# Control_Board.net
KiCad netlist of a schematic drawn in EAGLE
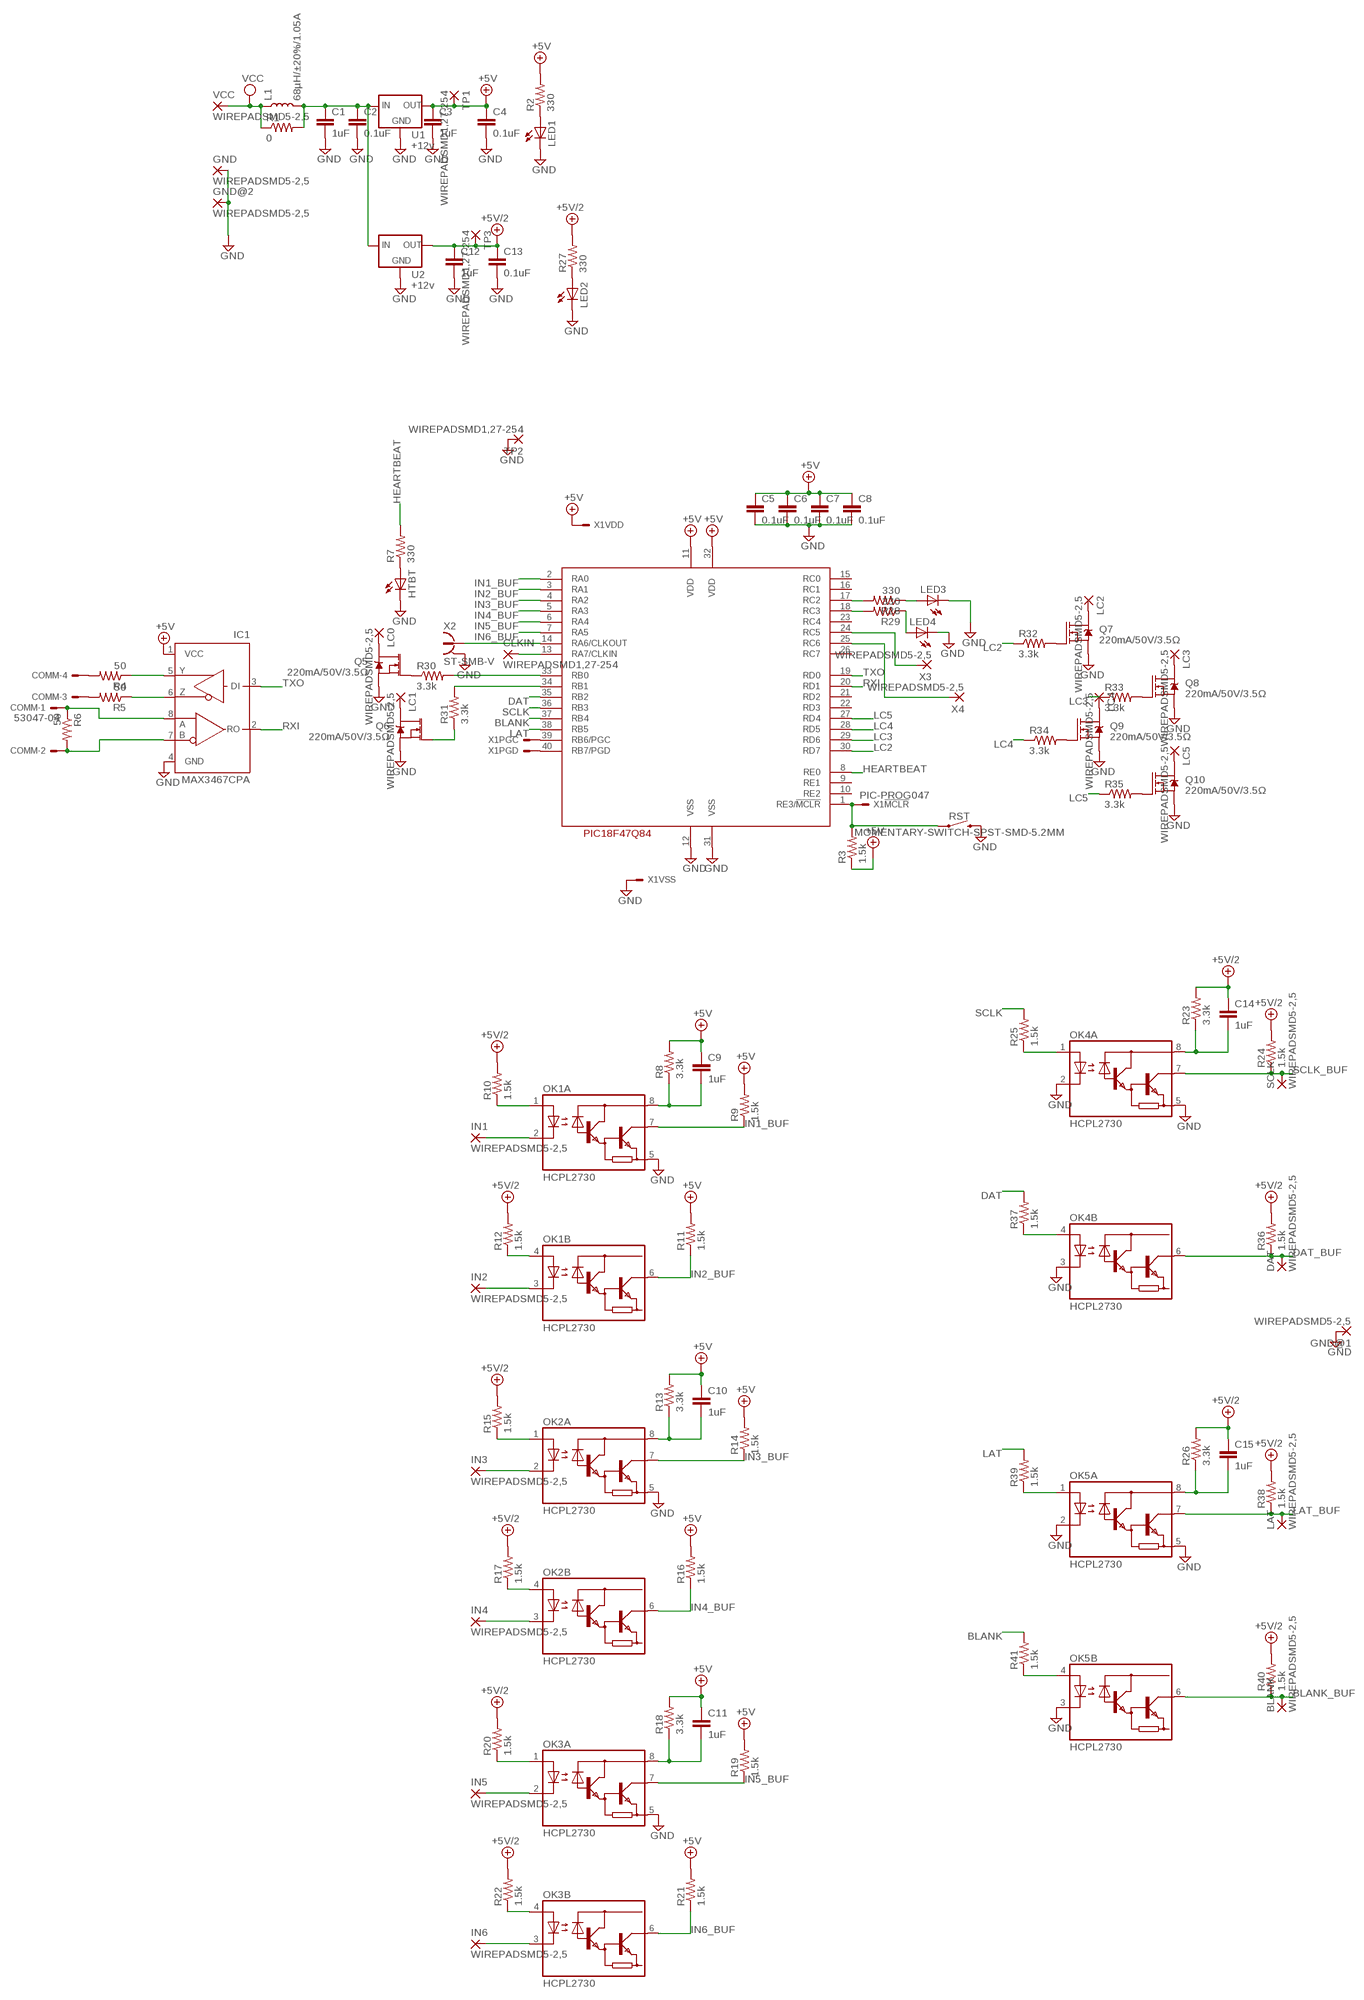
[diagram p0: schematic, sheet 1]

(export (version "E")
  (design (tool "Eeschema 10.0.6"))
  (components
    (comp (ref "BLANK")
      (value "WIREPADSMD5-2,5")
      (footprint "eagle-import:5-2,5")
      (libsource (lib "eagle-import") (part "WIREPADSMD5-2,5"))
    )
    (comp (ref "C1")
      (value "1uF")
      (footprint "eagle-import:C1206")
      (libsource (lib "eagle-import") (part "C-EUC1206"))
    )
    (comp (ref "C2")
      (value "0.1uF")
      (footprint "eagle-import:C1206")
      (libsource (lib "eagle-import") (part "C-EUC1206"))
    )
    (comp (ref "C3")
      (value "1uF")
      (footprint "eagle-import:C1206")
      (libsource (lib "eagle-import") (part "C-EUC1206"))
    )
    (comp (ref "C4")
      (value "0.1uF")
      (footprint "eagle-import:C1206")
      (libsource (lib "eagle-import") (part "C-EUC1206"))
    )
    (comp (ref "C5")
      (value "0.1uF")
      (footprint "eagle-import:C1206")
      (libsource (lib "eagle-import") (part "C-EUC1206"))
    )
    (comp (ref "C6")
      (value "0.1uF")
      (footprint "eagle-import:C1206")
      (libsource (lib "eagle-import") (part "C-EUC1206"))
    )
    (comp (ref "C7")
      (value "0.1uF")
      (footprint "eagle-import:C1206")
      (libsource (lib "eagle-import") (part "C-EUC1206"))
    )
    (comp (ref "C8")
      (value "0.1uF")
      (footprint "eagle-import:C1206")
      (libsource (lib "eagle-import") (part "C-EUC1206"))
    )
    (comp (ref "C9")
      (value "1uF")
      (footprint "eagle-import:C1206")
      (libsource (lib "eagle-import") (part "C-EUC1206"))
    )
    (comp (ref "C10")
      (value "1uF")
      (footprint "eagle-import:C1206")
      (libsource (lib "eagle-import") (part "C-EUC1206"))
    )
    (comp (ref "C11")
      (value "1uF")
      (footprint "eagle-import:C1206")
      (libsource (lib "eagle-import") (part "C-EUC1206"))
    )
    (comp (ref "C12")
      (value "1uF")
      (footprint "eagle-import:C1206")
      (libsource (lib "eagle-import") (part "C-EUC1206"))
    )
    (comp (ref "C13")
      (value "0.1uF")
      (footprint "eagle-import:C1206")
      (libsource (lib "eagle-import") (part "C-EUC1206"))
    )
    (comp (ref "C14")
      (value "1uF")
      (footprint "eagle-import:C1206")
      (libsource (lib "eagle-import") (part "C-EUC1206"))
    )
    (comp (ref "C15")
      (value "1uF")
      (footprint "eagle-import:C1206")
      (libsource (lib "eagle-import") (part "C-EUC1206"))
    )
    (comp (ref "CLKIN")
      (value "WIREPADSMD1,27-254")
      (footprint "eagle-import:SMD1,27-2,54")
      (libsource (lib "eagle-import") (part "WIREPADSMD1,27-254"))
    )
    (comp (ref "COMM")
      (value "53047-04")
      (footprint "eagle-import:53047-04")
      (fields (field (name "MF") "WALDOM/MOLEX") (field (name "MPN") "53047-0410"))
      (libsource (lib "eagle-import") (part "53?-04047"))
    )
    (comp (ref "DAT")
      (value "WIREPADSMD5-2,5")
      (footprint "eagle-import:5-2,5")
      (libsource (lib "eagle-import") (part "WIREPADSMD5-2,5"))
    )
    (comp (ref "GND")
      (value "WIREPADSMD5-2,5")
      (footprint "eagle-import:5-2,5")
      (libsource (lib "eagle-import") (part "WIREPADSMD5-2,5"))
    )
    (comp (ref "GND@1")
      (value "WIREPADSMD5-2,5")
      (footprint "eagle-import:5-2,5")
      (libsource (lib "eagle-import") (part "WIREPADSMD5-2,5"))
    )
    (comp (ref "GND@2")
      (value "WIREPADSMD5-2,5")
      (footprint "eagle-import:5-2,5")
      (libsource (lib "eagle-import") (part "WIREPADSMD5-2,5"))
    )
    (comp (ref "HTBT")
      (value "LEDCHIPLED_1206")
      (footprint "eagle-import:CHIPLED_1206")
      (libsource (lib "eagle-import") (part "LEDCHIPLED_1206"))
    )
    (comp (ref "IC1")
      (value "MAX3467CPA")
      (footprint "eagle-import:SO08")
      (libsource (lib "eagle-import") (part "MAX3467PAC"))
    )
    (comp (ref "IN1")
      (value "WIREPADSMD5-2,5")
      (footprint "eagle-import:5-2,5")
      (libsource (lib "eagle-import") (part "WIREPADSMD5-2,5"))
    )
    (comp (ref "IN2")
      (value "WIREPADSMD5-2,5")
      (footprint "eagle-import:5-2,5")
      (libsource (lib "eagle-import") (part "WIREPADSMD5-2,5"))
    )
    (comp (ref "IN3")
      (value "WIREPADSMD5-2,5")
      (footprint "eagle-import:5-2,5")
      (libsource (lib "eagle-import") (part "WIREPADSMD5-2,5"))
    )
    (comp (ref "IN4")
      (value "WIREPADSMD5-2,5")
      (footprint "eagle-import:5-2,5")
      (libsource (lib "eagle-import") (part "WIREPADSMD5-2,5"))
    )
    (comp (ref "IN5")
      (value "WIREPADSMD5-2,5")
      (footprint "eagle-import:5-2,5")
      (libsource (lib "eagle-import") (part "WIREPADSMD5-2,5"))
    )
    (comp (ref "IN6")
      (value "WIREPADSMD5-2,5")
      (footprint "eagle-import:5-2,5")
      (libsource (lib "eagle-import") (part "WIREPADSMD5-2,5"))
    )
    (comp (ref "L1")
      (value "68µH/±20%/1.05A")
      (footprint "eagle-import:CR75")
      (libsource (lib "eagle-import") (part "INDUCTOR-CR75-68UH"))
    )
    (comp (ref "LAT")
      (value "WIREPADSMD5-2,5")
      (footprint "eagle-import:5-2,5")
      (libsource (lib "eagle-import") (part "WIREPADSMD5-2,5"))
    )
    (comp (ref "LC0")
      (value "WIREPADSMD5-2,5")
      (footprint "eagle-import:5-2,5")
      (libsource (lib "eagle-import") (part "WIREPADSMD5-2,5"))
    )
    (comp (ref "LC1")
      (value "WIREPADSMD5-2,5")
      (footprint "eagle-import:5-2,5")
      (libsource (lib "eagle-import") (part "WIREPADSMD5-2,5"))
    )
    (comp (ref "LC2")
      (value "WIREPADSMD5-2,5")
      (footprint "eagle-import:5-2,5")
      (libsource (lib "eagle-import") (part "WIREPADSMD5-2,5"))
    )
    (comp (ref "LC3")
      (value "WIREPADSMD5-2,5")
      (footprint "eagle-import:5-2,5")
      (libsource (lib "eagle-import") (part "WIREPADSMD5-2,5"))
    )
    (comp (ref "LC4")
      (value "WIREPADSMD5-2,5")
      (footprint "eagle-import:5-2,5")
      (libsource (lib "eagle-import") (part "WIREPADSMD5-2,5"))
    )
    (comp (ref "LC5")
      (value "WIREPADSMD5-2,5")
      (footprint "eagle-import:5-2,5")
      (libsource (lib "eagle-import") (part "WIREPADSMD5-2,5"))
    )
    (comp (ref "LED1")
      (value "LEDCHIPLED_1206")
      (footprint "eagle-import:CHIPLED_1206")
      (libsource (lib "eagle-import") (part "LEDCHIPLED_1206"))
    )
    (comp (ref "LED2")
      (value "LEDCHIPLED_1206")
      (footprint "eagle-import:CHIPLED_1206")
      (libsource (lib "eagle-import") (part "LEDCHIPLED_1206"))
    )
    (comp (ref "LED3")
      (value "LEDCHIPLED_1206")
      (footprint "eagle-import:CHIPLED_1206")
      (libsource (lib "eagle-import") (part "LEDCHIPLED_1206"))
    )
    (comp (ref "LED4")
      (value "LEDCHIPLED_1206")
      (footprint "eagle-import:CHIPLED_1206")
      (libsource (lib "eagle-import") (part "LEDCHIPLED_1206"))
    )
    (comp (ref "OK1")
      (value "HCPL2730")
      (footprint "eagle-import:DIL08")
      (fields (field (name "MF") "AGILENT TECHNOLOGIES") (field (name "MPN") "HCPL-2730-000E"))
      (libsource (lib "eagle-import") (part "HCPL2730"))
    )
    (comp (ref "OK2")
      (value "HCPL2730")
      (footprint "eagle-import:DIL08")
      (fields (field (name "MF") "AGILENT TECHNOLOGIES") (field (name "MPN") "HCPL-2730-000E"))
      (libsource (lib "eagle-import") (part "HCPL2730"))
    )
    (comp (ref "OK3")
      (value "HCPL2730")
      (footprint "eagle-import:DIL08")
      (fields (field (name "MF") "AGILENT TECHNOLOGIES") (field (name "MPN") "HCPL-2730-000E"))
      (libsource (lib "eagle-import") (part "HCPL2730"))
    )
    (comp (ref "OK4")
      (value "HCPL2730")
      (footprint "eagle-import:DIL08")
      (fields (field (name "MF") "AGILENT TECHNOLOGIES") (field (name "MPN") "HCPL-2730-000E"))
      (libsource (lib "eagle-import") (part "HCPL2730"))
    )
    (comp (ref "OK5")
      (value "HCPL2730")
      (footprint "eagle-import:DIL08")
      (fields (field (name "MF") "AGILENT TECHNOLOGIES") (field (name "MPN") "HCPL-2730-000E"))
      (libsource (lib "eagle-import") (part "HCPL2730"))
    )
    (comp (ref "Q5")
      (value "220mA/50V/3.5Ω")
      (footprint "eagle-import:SOT23-3")
      (libsource (lib "eagle-import") (part "MOSFET-NCH-BSS138"))
    )
    (comp (ref "Q6")
      (value "220mA/50V/3.5Ω")
      (footprint "eagle-import:SOT23-3")
      (libsource (lib "eagle-import") (part "MOSFET-NCH-BSS138"))
    )
    (comp (ref "Q7")
      (value "220mA/50V/3.5Ω")
      (footprint "eagle-import:SOT23-3")
      (libsource (lib "eagle-import") (part "MOSFET-NCH-BSS138"))
    )
    (comp (ref "Q8")
      (value "220mA/50V/3.5Ω")
      (footprint "eagle-import:SOT23-3")
      (libsource (lib "eagle-import") (part "MOSFET-NCH-BSS138"))
    )
    (comp (ref "Q9")
      (value "220mA/50V/3.5Ω")
      (footprint "eagle-import:SOT23-3")
      (libsource (lib "eagle-import") (part "MOSFET-NCH-BSS138"))
    )
    (comp (ref "Q10")
      (value "220mA/50V/3.5Ω")
      (footprint "eagle-import:SOT23-3")
      (libsource (lib "eagle-import") (part "MOSFET-NCH-BSS138"))
    )
    (comp (ref "R1")
      (value "0")
      (footprint "eagle-import:M1206")
      (libsource (lib "eagle-import") (part "R-US_M1206"))
    )
    (comp (ref "R2")
      (value "330")
      (footprint "eagle-import:M1206")
      (libsource (lib "eagle-import") (part "R-US_M1206"))
    )
    (comp (ref "R3")
      (value "1.5k")
      (footprint "eagle-import:M1206")
      (libsource (lib "eagle-import") (part "R-US_M1206"))
    )
    (comp (ref "R4")
      (value "50")
      (footprint "eagle-import:M1206")
      (libsource (lib "eagle-import") (part "R-US_M1206"))
    )
    (comp (ref "R5")
      (value "50")
      (footprint "eagle-import:M1206")
      (libsource (lib "eagle-import") (part "R-US_M1206"))
    )
    (comp (ref "R6")
      (value "50")
      (footprint "eagle-import:M1206")
      (libsource (lib "eagle-import") (part "R-US_M1206"))
    )
    (comp (ref "R7")
      (value "330")
      (footprint "eagle-import:M1206")
      (libsource (lib "eagle-import") (part "R-US_M1206"))
    )
    (comp (ref "R8")
      (value "3.3k")
      (footprint "eagle-import:M1206")
      (libsource (lib "eagle-import") (part "R-US_M1206"))
    )
    (comp (ref "R9")
      (value "1.5k")
      (footprint "eagle-import:M1206")
      (libsource (lib "eagle-import") (part "R-US_M1206"))
    )
    (comp (ref "R10")
      (value "1.5k")
      (footprint "eagle-import:M1206")
      (libsource (lib "eagle-import") (part "R-US_M1206"))
    )
    (comp (ref "R11")
      (value "1.5k")
      (footprint "eagle-import:M1206")
      (libsource (lib "eagle-import") (part "R-US_M1206"))
    )
    (comp (ref "R12")
      (value "1.5k")
      (footprint "eagle-import:M1206")
      (libsource (lib "eagle-import") (part "R-US_M1206"))
    )
    (comp (ref "R13")
      (value "3.3k")
      (footprint "eagle-import:M1206")
      (libsource (lib "eagle-import") (part "R-US_M1206"))
    )
    (comp (ref "R14")
      (value "1.5k")
      (footprint "eagle-import:M1206")
      (libsource (lib "eagle-import") (part "R-US_M1206"))
    )
    (comp (ref "R15")
      (value "1.5k")
      (footprint "eagle-import:M1206")
      (libsource (lib "eagle-import") (part "R-US_M1206"))
    )
    (comp (ref "R16")
      (value "1.5k")
      (footprint "eagle-import:M1206")
      (libsource (lib "eagle-import") (part "R-US_M1206"))
    )
    (comp (ref "R17")
      (value "1.5k")
      (footprint "eagle-import:M1206")
      (libsource (lib "eagle-import") (part "R-US_M1206"))
    )
    (comp (ref "R18")
      (value "3.3k")
      (footprint "eagle-import:M1206")
      (libsource (lib "eagle-import") (part "R-US_M1206"))
    )
    (comp (ref "R19")
      (value "1.5k")
      (footprint "eagle-import:M1206")
      (libsource (lib "eagle-import") (part "R-US_M1206"))
    )
    (comp (ref "R20")
      (value "1.5k")
      (footprint "eagle-import:M1206")
      (libsource (lib "eagle-import") (part "R-US_M1206"))
    )
    (comp (ref "R21")
      (value "1.5k")
      (footprint "eagle-import:M1206")
      (libsource (lib "eagle-import") (part "R-US_M1206"))
    )
    (comp (ref "R22")
      (value "1.5k")
      (footprint "eagle-import:M1206")
      (libsource (lib "eagle-import") (part "R-US_M1206"))
    )
    (comp (ref "R23")
      (value "3.3k")
      (footprint "eagle-import:M1206")
      (libsource (lib "eagle-import") (part "R-US_M1206"))
    )
    (comp (ref "R24")
      (value "1.5k")
      (footprint "eagle-import:M1206")
      (libsource (lib "eagle-import") (part "R-US_M1206"))
    )
    (comp (ref "R25")
      (value "1.5k")
      (footprint "eagle-import:M1206")
      (libsource (lib "eagle-import") (part "R-US_M1206"))
    )
    (comp (ref "R26")
      (value "3.3k")
      (footprint "eagle-import:M1206")
      (libsource (lib "eagle-import") (part "R-US_M1206"))
    )
    (comp (ref "R27")
      (value "330")
      (footprint "eagle-import:M1206")
      (libsource (lib "eagle-import") (part "R-US_M1206"))
    )
    (comp (ref "R28")
      (value "330")
      (footprint "eagle-import:M1206")
      (libsource (lib "eagle-import") (part "R-US_M1206"))
    )
    (comp (ref "R29")
      (value "330")
      (footprint "eagle-import:M1206")
      (libsource (lib "eagle-import") (part "R-US_M1206"))
    )
    (comp (ref "R30")
      (value "3.3k")
      (footprint "eagle-import:M1206")
      (libsource (lib "eagle-import") (part "R-US_M1206"))
    )
    (comp (ref "R31")
      (value "3.3k")
      (footprint "eagle-import:M1206")
      (libsource (lib "eagle-import") (part "R-US_M1206"))
    )
    (comp (ref "R32")
      (value "3.3k")
      (footprint "eagle-import:M1206")
      (libsource (lib "eagle-import") (part "R-US_M1206"))
    )
    (comp (ref "R33")
      (value "3.3k")
      (footprint "eagle-import:M1206")
      (libsource (lib "eagle-import") (part "R-US_M1206"))
    )
    (comp (ref "R34")
      (value "3.3k")
      (footprint "eagle-import:M1206")
      (libsource (lib "eagle-import") (part "R-US_M1206"))
    )
    (comp (ref "R35")
      (value "3.3k")
      (footprint "eagle-import:M1206")
      (libsource (lib "eagle-import") (part "R-US_M1206"))
    )
    (comp (ref "R36")
      (value "1.5k")
      (footprint "eagle-import:M1206")
      (libsource (lib "eagle-import") (part "R-US_M1206"))
    )
    (comp (ref "R37")
      (value "1.5k")
      (footprint "eagle-import:M1206")
      (libsource (lib "eagle-import") (part "R-US_M1206"))
    )
    (comp (ref "R38")
      (value "1.5k")
      (footprint "eagle-import:M1206")
      (libsource (lib "eagle-import") (part "R-US_M1206"))
    )
    (comp (ref "R39")
      (value "1.5k")
      (footprint "eagle-import:M1206")
      (libsource (lib "eagle-import") (part "R-US_M1206"))
    )
    (comp (ref "R40")
      (value "1.5k")
      (footprint "eagle-import:M1206")
      (libsource (lib "eagle-import") (part "R-US_M1206"))
    )
    (comp (ref "R41")
      (value "1.5k")
      (footprint "eagle-import:M1206")
      (libsource (lib "eagle-import") (part "R-US_M1206"))
    )
    (comp (ref "RST")
      (value "MOMENTARY-SWITCH-SPST-SMD-5.2MM")
      (footprint "eagle-import:TACTILE_SWITCH_SMD_5.2MM")
      (libsource (lib "eagle-import") (part "MOMENTARY-SWITCH-SPST-SMD-5.2MM"))
    )
    (comp (ref "SCLK")
      (value "WIREPADSMD5-2,5")
      (footprint "eagle-import:5-2,5")
      (libsource (lib "eagle-import") (part "WIREPADSMD5-2,5"))
    )
    (comp (ref "TP1")
      (value "WIREPADSMD1,27-254")
      (footprint "eagle-import:SMD1,27-2,54")
      (libsource (lib "eagle-import") (part "WIREPADSMD1,27-254"))
    )
    (comp (ref "TP2")
      (value "WIREPADSMD1,27-254")
      (footprint "eagle-import:SMD1,27-2,54")
      (libsource (lib "eagle-import") (part "WIREPADSMD1,27-254"))
    )
    (comp (ref "TP3")
      (value "WIREPADSMD1,27-254")
      (footprint "eagle-import:SMD1,27-2,54")
      (libsource (lib "eagle-import") (part "WIREPADSMD1,27-254"))
    )
    (comp (ref "U$1")
      (value "PIC18F47Q84")
      (footprint "eagle-import:DIL40")
      (libsource (lib "eagle-import") (part "PIC18F47Q84"))
    )
    (comp (ref "U1")
      (value "+12v")
      (footprint "eagle-import:TO-252")
      (libsource (lib "eagle-import") (part "V_REG_78XX7812"))
    )
    (comp (ref "U2")
      (value "+12v")
      (footprint "eagle-import:TO-252")
      (libsource (lib "eagle-import") (part "V_REG_78XX7812"))
    )
    (comp (ref "VCC")
      (value "WIREPADSMD5-2,5")
      (footprint "eagle-import:5-2,5")
      (libsource (lib "eagle-import") (part "WIREPADSMD5-2,5"))
    )
    (comp (ref "X1")
      (value "PIC-PROG047")
      (footprint "eagle-import:53047-05")
      (fields (field (name "MF") "MOLEX") (field (name "MPN") "53047-0510"))
      (libsource (lib "eagle-import") (part "PIC-PROG047"))
    )
    (comp (ref "X2")
      (value "ST-SMB-V")
      (footprint "eagle-import:ST-SMB-V")
      (libsource (lib "eagle-import") (part "ST-SMB-V"))
    )
    (comp (ref "X3")
      (value "WIREPADSMD5-2,5")
      (footprint "eagle-import:5-2,5")
      (libsource (lib "eagle-import") (part "WIREPADSMD5-2,5"))
    )
    (comp (ref "X4")
      (value "WIREPADSMD5-2,5")
      (footprint "eagle-import:5-2,5")
      (libsource (lib "eagle-import") (part "WIREPADSMD5-2,5"))
    )
  )
  (nets
    (net (code "1") (name "+5V") (class "Default")
      (node (ref "C10") (pin "1") (pinfunction "1_1") (pintype "passive"))
      (node (ref "C11") (pin "1") (pinfunction "1_1") (pintype "passive"))
      (node (ref "C3") (pin "1") (pinfunction "1_1") (pintype "passive"))
      (node (ref "C4") (pin "1") (pinfunction "1_1") (pintype "passive"))
      (node (ref "C5") (pin "1") (pinfunction "1_1") (pintype "passive"))
      (node (ref "C6") (pin "1") (pinfunction "1_1") (pintype "passive"))
      (node (ref "C7") (pin "1") (pinfunction "1_1") (pintype "passive"))
      (node (ref "C8") (pin "1") (pinfunction "1_1") (pintype "passive"))
      (node (ref "C9") (pin "1") (pinfunction "1_1") (pintype "passive"))
      (node (ref "IC1") (pin "1") (pinfunction "VCC_1") (pintype "power_in"))
      (node (ref "R11") (pin "2") (pinfunction "2_2") (pintype "passive"))
      (node (ref "R13") (pin "2") (pinfunction "2_2") (pintype "passive"))
      (node (ref "R14") (pin "2") (pinfunction "2_2") (pintype "passive"))
      (node (ref "R16") (pin "2") (pinfunction "2_2") (pintype "passive"))
      (node (ref "R18") (pin "2") (pinfunction "2_2") (pintype "passive"))
      (node (ref "R19") (pin "2") (pinfunction "2_2") (pintype "passive"))
      (node (ref "R2") (pin "2") (pinfunction "2_2") (pintype "passive"))
      (node (ref "R21") (pin "2") (pinfunction "2_2") (pintype "passive"))
      (node (ref "R3") (pin "1") (pinfunction "1_1") (pintype "passive"))
      (node (ref "R8") (pin "2") (pinfunction "2_2") (pintype "passive"))
      (node (ref "R9") (pin "2") (pinfunction "2_2") (pintype "passive"))
      (node (ref "TP1") (pin "1") (pinfunction "P_1") (pintype "passive"))
      (node (ref "U$1") (pin "11") (pinfunction "VDD_11") (pintype "bidirectional"))
      (node (ref "U$1") (pin "32") (pinfunction "VDD_32") (pintype "bidirectional"))
      (node (ref "U1") (pin "2") (pinfunction "OUT_2") (pintype "passive"))
      (node (ref "X1") (pin "2") (pinfunction "S_2") (pintype "passive"))
    )
    (net (code "2") (name "+5V{slash}2") (class "Default")
      (node (ref "C12") (pin "1") (pinfunction "1_1") (pintype "passive"))
      (node (ref "C13") (pin "1") (pinfunction "1_1") (pintype "passive"))
      (node (ref "C14") (pin "1") (pinfunction "1_1") (pintype "passive"))
      (node (ref "C15") (pin "1") (pinfunction "1_1") (pintype "passive"))
      (node (ref "R10") (pin "2") (pinfunction "2_2") (pintype "passive"))
      (node (ref "R12") (pin "2") (pinfunction "2_2") (pintype "passive"))
      (node (ref "R15") (pin "2") (pinfunction "2_2") (pintype "passive"))
      (node (ref "R17") (pin "2") (pinfunction "2_2") (pintype "passive"))
      (node (ref "R20") (pin "2") (pinfunction "2_2") (pintype "passive"))
      (node (ref "R22") (pin "2") (pinfunction "2_2") (pintype "passive"))
      (node (ref "R23") (pin "2") (pinfunction "2_2") (pintype "passive"))
      (node (ref "R24") (pin "2") (pinfunction "2_2") (pintype "passive"))
      (node (ref "R26") (pin "2") (pinfunction "2_2") (pintype "passive"))
      (node (ref "R27") (pin "2") (pinfunction "2_2") (pintype "passive"))
      (node (ref "R36") (pin "2") (pinfunction "2_2") (pintype "passive"))
      (node (ref "R38") (pin "2") (pinfunction "2_2") (pintype "passive"))
      (node (ref "R40") (pin "2") (pinfunction "2_2") (pintype "passive"))
      (node (ref "TP3") (pin "1") (pinfunction "P_1") (pintype "passive"))
      (node (ref "U2") (pin "2") (pinfunction "OUT_2") (pintype "passive"))
    )
    (net (code "3") (name "/BLANK") (class "Default")
      (node (ref "R41") (pin "2") (pinfunction "2_2") (pintype "passive"))
      (node (ref "U$1") (pin "37") (pinfunction "RB4_37") (pintype "bidirectional"))
    )
    (net (code "4") (name "/BLANK_BUF") (class "Default")
      (node (ref "BLANK") (pin "1") (pinfunction "P_1") (pintype "passive"))
      (node (ref "OK5") (pin "6") (pinfunction "VO2_6") (pintype "passive"))
      (node (ref "R40") (pin "1") (pinfunction "1_1") (pintype "passive"))
    )
    (net (code "5") (name "/DAT") (class "Default")
      (node (ref "R37") (pin "2") (pinfunction "2_2") (pintype "passive"))
      (node (ref "U$1") (pin "35") (pinfunction "RB2_35") (pintype "bidirectional"))
    )
    (net (code "6") (name "/DAT_BUF") (class "Default")
      (node (ref "DAT") (pin "1") (pinfunction "P_1") (pintype "passive"))
      (node (ref "OK4") (pin "6") (pinfunction "VO2_6") (pintype "passive"))
      (node (ref "R36") (pin "1") (pinfunction "1_1") (pintype "passive"))
    )
    (net (code "7") (name "/HEARTBEAT") (class "Default")
      (node (ref "R7") (pin "2") (pinfunction "2_2") (pintype "passive"))
      (node (ref "U$1") (pin "8") (pinfunction "RE0_8") (pintype "bidirectional"))
    )
    (net (code "8") (name "/IN1_BUF") (class "Default")
      (node (ref "OK1") (pin "7") (pinfunction "VO1_7") (pintype "passive"))
      (node (ref "R9") (pin "1") (pinfunction "1_1") (pintype "passive"))
      (node (ref "U$1") (pin "2") (pinfunction "RA0_2") (pintype "bidirectional"))
    )
    (net (code "9") (name "/IN2_BUF") (class "Default")
      (node (ref "OK1") (pin "6") (pinfunction "VO2_6") (pintype "passive"))
      (node (ref "R11") (pin "1") (pinfunction "1_1") (pintype "passive"))
      (node (ref "U$1") (pin "3") (pinfunction "RA1_3") (pintype "bidirectional"))
    )
    (net (code "10") (name "/IN3_BUF") (class "Default")
      (node (ref "OK2") (pin "7") (pinfunction "VO1_7") (pintype "passive"))
      (node (ref "R14") (pin "1") (pinfunction "1_1") (pintype "passive"))
      (node (ref "U$1") (pin "4") (pinfunction "RA2_4") (pintype "bidirectional"))
    )
    (net (code "11") (name "/IN4_BUF") (class "Default")
      (node (ref "OK2") (pin "6") (pinfunction "VO2_6") (pintype "passive"))
      (node (ref "R16") (pin "1") (pinfunction "1_1") (pintype "passive"))
      (node (ref "U$1") (pin "5") (pinfunction "RA3_5") (pintype "bidirectional"))
    )
    (net (code "12") (name "/IN5_BUF") (class "Default")
      (node (ref "OK3") (pin "7") (pinfunction "VO1_7") (pintype "passive"))
      (node (ref "R19") (pin "1") (pinfunction "1_1") (pintype "passive"))
      (node (ref "U$1") (pin "6") (pinfunction "RA4_6") (pintype "bidirectional"))
    )
    (net (code "13") (name "/IN6_BUF") (class "Default")
      (node (ref "OK3") (pin "6") (pinfunction "VO2_6") (pintype "passive"))
      (node (ref "R21") (pin "1") (pinfunction "1_1") (pintype "passive"))
      (node (ref "U$1") (pin "7") (pinfunction "RA5_7") (pintype "bidirectional"))
    )
    (net (code "14") (name "/LAT") (class "Default")
      (node (ref "R39") (pin "2") (pinfunction "2_2") (pintype "passive"))
      (node (ref "U$1") (pin "38") (pinfunction "RB5_38") (pintype "bidirectional"))
    )
    (net (code "15") (name "/LAT_BUF") (class "Default")
      (node (ref "LAT") (pin "1") (pinfunction "P_1") (pintype "passive"))
      (node (ref "OK5") (pin "7") (pinfunction "VO1_7") (pintype "passive"))
      (node (ref "R38") (pin "1") (pinfunction "1_1") (pintype "passive"))
    )
    (net (code "16") (name "/LC2") (class "Default")
      (node (ref "R32") (pin "1") (pinfunction "1_1") (pintype "passive"))
      (node (ref "U$1") (pin "30") (pinfunction "RD7_30") (pintype "bidirectional"))
    )
    (net (code "17") (name "/LC3") (class "Default")
      (node (ref "R33") (pin "1") (pinfunction "1_1") (pintype "passive"))
      (node (ref "U$1") (pin "29") (pinfunction "RD6_29") (pintype "bidirectional"))
    )
    (net (code "18") (name "/LC4") (class "Default")
      (node (ref "R34") (pin "1") (pinfunction "1_1") (pintype "passive"))
      (node (ref "U$1") (pin "28") (pinfunction "RD5_28") (pintype "bidirectional"))
    )
    (net (code "19") (name "/LC5") (class "Default")
      (node (ref "R35") (pin "1") (pinfunction "1_1") (pintype "passive"))
      (node (ref "U$1") (pin "27") (pinfunction "RD4_27") (pintype "bidirectional"))
    )
    (net (code "20") (name "/RXI") (class "Default")
      (node (ref "IC1") (pin "2") (pinfunction "RO_2") (pintype "output"))
      (node (ref "U$1") (pin "20") (pinfunction "RD1_20") (pintype "bidirectional"))
    )
    (net (code "21") (name "/SCLK") (class "Default")
      (node (ref "R25") (pin "2") (pinfunction "2_2") (pintype "passive"))
      (node (ref "U$1") (pin "36") (pinfunction "RB3_36") (pintype "bidirectional"))
    )
    (net (code "22") (name "/SCLK_BUF") (class "Default")
      (node (ref "OK4") (pin "7") (pinfunction "VO1_7") (pintype "passive"))
      (node (ref "R24") (pin "1") (pinfunction "1_1") (pintype "passive"))
      (node (ref "SCLK") (pin "1") (pinfunction "P_1") (pintype "passive"))
    )
    (net (code "23") (name "/TXO") (class "Default")
      (node (ref "IC1") (pin "3") (pinfunction "DI_3") (pintype "input"))
      (node (ref "U$1") (pin "19") (pinfunction "RD0_19") (pintype "bidirectional"))
    )
    (net (code "24") (name "GND") (class "Default")
      (node (ref "C1") (pin "2") (pinfunction "2_2") (pintype "passive"))
      (node (ref "C12") (pin "2") (pinfunction "2_2") (pintype "passive"))
      (node (ref "C13") (pin "2") (pinfunction "2_2") (pintype "passive"))
      (node (ref "C2") (pin "2") (pinfunction "2_2") (pintype "passive"))
      (node (ref "C3") (pin "2") (pinfunction "2_2") (pintype "passive"))
      (node (ref "C4") (pin "2") (pinfunction "2_2") (pintype "passive"))
      (node (ref "C5") (pin "2") (pinfunction "2_2") (pintype "passive"))
      (node (ref "C6") (pin "2") (pinfunction "2_2") (pintype "passive"))
      (node (ref "C7") (pin "2") (pinfunction "2_2") (pintype "passive"))
      (node (ref "C8") (pin "2") (pinfunction "2_2") (pintype "passive"))
      (node (ref "GND") (pin "1") (pinfunction "P_1") (pintype "passive"))
      (node (ref "GND@1") (pin "1") (pinfunction "P_1") (pintype "passive"))
      (node (ref "GND@2") (pin "1") (pinfunction "P_1") (pintype "passive"))
      (node (ref "HTBT") (pin "C") (pinfunction "C_C") (pintype "passive"))
      (node (ref "IC1") (pin "4") (pinfunction "GND_4") (pintype "power_in"))
      (node (ref "LED1") (pin "C") (pinfunction "C_C") (pintype "passive"))
      (node (ref "LED2") (pin "C") (pinfunction "C_C") (pintype "passive"))
      (node (ref "LED3") (pin "C") (pinfunction "C_C") (pintype "passive"))
      (node (ref "LED4") (pin "C") (pinfunction "C_C") (pintype "passive"))
      (node (ref "OK1") (pin "5") (pinfunction "GND_5") (pintype "passive"))
      (node (ref "OK2") (pin "5") (pinfunction "GND_5") (pintype "passive"))
      (node (ref "OK3") (pin "5") (pinfunction "GND_5") (pintype "passive"))
      (node (ref "OK4") (pin "2") (pinfunction "C1_2") (pintype "passive"))
      (node (ref "OK4") (pin "3") (pinfunction "C2_3") (pintype "passive"))
      (node (ref "OK4") (pin "5") (pinfunction "GND_5") (pintype "passive"))
      (node (ref "OK5") (pin "2") (pinfunction "C1_2") (pintype "passive"))
      (node (ref "OK5") (pin "3") (pinfunction "C2_3") (pintype "passive"))
      (node (ref "OK5") (pin "5") (pinfunction "GND_5") (pintype "passive"))
      (node (ref "Q10") (pin "2") (pinfunction "S_2") (pintype "bidirectional"))
      (node (ref "Q5") (pin "2") (pinfunction "S_2") (pintype "bidirectional"))
      (node (ref "Q6") (pin "2") (pinfunction "S_2") (pintype "bidirectional"))
      (node (ref "Q7") (pin "2") (pinfunction "S_2") (pintype "bidirectional"))
      (node (ref "Q8") (pin "2") (pinfunction "S_2") (pintype "bidirectional"))
      (node (ref "Q9") (pin "2") (pinfunction "S_2") (pintype "bidirectional"))
      (node (ref "RST") (pin "3") (pinfunction "2_3") (pintype "passive"))
      (node (ref "TP2") (pin "1") (pinfunction "P_1") (pintype "passive"))
      (node (ref "U$1") (pin "12") (pinfunction "VSS_12") (pintype "bidirectional"))
      (node (ref "U$1") (pin "31") (pinfunction "VSS_31") (pintype "bidirectional"))
      (node (ref "U1") (pin "3") (pinfunction "GND_3") (pintype "input"))
      (node (ref "U2") (pin "3") (pinfunction "GND_3") (pintype "input"))
      (node (ref "X1") (pin "3") (pinfunction "S_3") (pintype "passive"))
      (node (ref "X2") (pin "2") (pinfunction "2_2") (pintype "passive"))
      (node (ref "X2") (pin "3") (pinfunction "2_3") (pintype "passive"))
      (node (ref "X2") (pin "4") (pinfunction "2_4") (pintype "passive"))
      (node (ref "X2") (pin "5") (pinfunction "2_5") (pintype "passive"))
    )
    (net (code "25") (name "Net-(CLKIN-P)") (class "Default")
      (node (ref "CLKIN") (pin "1") (pinfunction "P_1") (pintype "passive"))
      (node (ref "U$1") (pin "13") (pinfunction "RA7/CLKIN_13") (pintype "bidirectional"))
    )
    (net (code "26") (name "Net-(COMMA-S)") (class "Default")
      (node (ref "COMM") (pin "1") (pinfunction "S_1") (pintype "passive"))
      (node (ref "IC1") (pin "8") (pinfunction "A_8") (pintype "passive"))
      (node (ref "R6") (pin "1") (pinfunction "1_1") (pintype "passive"))
    )
    (net (code "27") (name "Net-(COMMB-S)") (class "Default")
      (node (ref "COMM") (pin "2") (pinfunction "S_2") (pintype "passive"))
      (node (ref "IC1") (pin "7") (pinfunction "B_7") (pintype "passive"))
      (node (ref "R6") (pin "2") (pinfunction "2_2") (pintype "passive"))
    )
    (net (code "28") (name "Net-(COMMC-S)") (class "Default")
      (node (ref "COMM") (pin "3") (pinfunction "S_3") (pintype "passive"))
      (node (ref "R5") (pin "2") (pinfunction "2_2") (pintype "passive"))
    )
    (net (code "29") (name "Net-(COMMD-S)") (class "Default")
      (node (ref "COMM") (pin "4") (pinfunction "S_4") (pintype "passive"))
      (node (ref "R4") (pin "2") (pinfunction "2_2") (pintype "passive"))
    )
    (net (code "30") (name "Net-(HTBT-PadA)") (class "Default")
      (node (ref "HTBT") (pin "A") (pinfunction "A_A") (pintype "passive"))
      (node (ref "R7") (pin "1") (pinfunction "1_1") (pintype "passive"))
    )
    (net (code "31") (name "Net-(IC1-Y)") (class "Default")
      (node (ref "IC1") (pin "5") (pinfunction "Y_5") (pintype "passive"))
      (node (ref "R4") (pin "1") (pinfunction "1_1") (pintype "passive"))
    )
    (net (code "32") (name "Net-(IC1-Z)") (class "Default")
      (node (ref "IC1") (pin "6") (pinfunction "Z_6") (pintype "passive"))
      (node (ref "R5") (pin "1") (pinfunction "1_1") (pintype "passive"))
    )
    (net (code "33") (name "Net-(IN1-P)") (class "Default")
      (node (ref "IN1") (pin "1") (pinfunction "P_1") (pintype "passive"))
      (node (ref "OK1") (pin "2") (pinfunction "C1_2") (pintype "passive"))
    )
    (net (code "34") (name "Net-(IN2-P)") (class "Default")
      (node (ref "IN2") (pin "1") (pinfunction "P_1") (pintype "passive"))
      (node (ref "OK1") (pin "3") (pinfunction "C2_3") (pintype "passive"))
    )
    (net (code "35") (name "Net-(IN3-P)") (class "Default")
      (node (ref "IN3") (pin "1") (pinfunction "P_1") (pintype "passive"))
      (node (ref "OK2") (pin "2") (pinfunction "C1_2") (pintype "passive"))
    )
    (net (code "36") (name "Net-(IN4-P)") (class "Default")
      (node (ref "IN4") (pin "1") (pinfunction "P_1") (pintype "passive"))
      (node (ref "OK2") (pin "3") (pinfunction "C2_3") (pintype "passive"))
    )
    (net (code "37") (name "Net-(IN5-P)") (class "Default")
      (node (ref "IN5") (pin "1") (pinfunction "P_1") (pintype "passive"))
      (node (ref "OK3") (pin "2") (pinfunction "C1_2") (pintype "passive"))
    )
    (net (code "38") (name "Net-(IN6-P)") (class "Default")
      (node (ref "IN6") (pin "1") (pinfunction "P_1") (pintype "passive"))
      (node (ref "OK3") (pin "3") (pinfunction "C2_3") (pintype "passive"))
    )
    (net (code "39") (name "Net-(L1-2)") (class "Default")
      (node (ref "C1") (pin "1") (pinfunction "1_1") (pintype "passive"))
      (node (ref "C2") (pin "1") (pinfunction "1_1") (pintype "passive"))
      (node (ref "L1") (pin "P$2") (pinfunction "2_P$2") (pintype "passive"))
      (node (ref "R1") (pin "2") (pinfunction "2_2") (pintype "passive"))
      (node (ref "U1") (pin "1") (pinfunction "IN_1") (pintype "input"))
      (node (ref "U2") (pin "1") (pinfunction "IN_1") (pintype "input"))
    )
    (net (code "40") (name "Net-(LC0-P)") (class "Default")
      (node (ref "LC0") (pin "1") (pinfunction "P_1") (pintype "passive"))
      (node (ref "Q5") (pin "3") (pinfunction "D_3") (pintype "bidirectional"))
    )
    (net (code "41") (name "Net-(LC1-P)") (class "Default")
      (node (ref "LC1") (pin "1") (pinfunction "P_1") (pintype "passive"))
      (node (ref "Q6") (pin "3") (pinfunction "D_3") (pintype "bidirectional"))
    )
    (net (code "42") (name "Net-(LC2-P)") (class "Default")
      (node (ref "LC2") (pin "1") (pinfunction "P_1") (pintype "passive"))
      (node (ref "Q7") (pin "3") (pinfunction "D_3") (pintype "bidirectional"))
    )
    (net (code "43") (name "Net-(LC3-P)") (class "Default")
      (node (ref "LC3") (pin "1") (pinfunction "P_1") (pintype "passive"))
      (node (ref "Q8") (pin "3") (pinfunction "D_3") (pintype "bidirectional"))
    )
    (net (code "44") (name "Net-(LC4-P)") (class "Default")
      (node (ref "LC4") (pin "1") (pinfunction "P_1") (pintype "passive"))
      (node (ref "Q9") (pin "3") (pinfunction "D_3") (pintype "bidirectional"))
    )
    (net (code "45") (name "Net-(LC5-P)") (class "Default")
      (node (ref "LC5") (pin "1") (pinfunction "P_1") (pintype "passive"))
      (node (ref "Q10") (pin "3") (pinfunction "D_3") (pintype "bidirectional"))
    )
    (net (code "46") (name "Net-(LED1-PadA)") (class "Default")
      (node (ref "LED1") (pin "A") (pinfunction "A_A") (pintype "passive"))
      (node (ref "R2") (pin "1") (pinfunction "1_1") (pintype "passive"))
    )
    (net (code "47") (name "Net-(LED2-PadA)") (class "Default")
      (node (ref "LED2") (pin "A") (pinfunction "A_A") (pintype "passive"))
      (node (ref "R27") (pin "1") (pinfunction "1_1") (pintype "passive"))
    )
    (net (code "48") (name "Net-(LED3-PadA)") (class "Default")
      (node (ref "LED3") (pin "A") (pinfunction "A_A") (pintype "passive"))
      (node (ref "R28") (pin "1") (pinfunction "1_1") (pintype "passive"))
    )
    (net (code "49") (name "Net-(LED4-PadA)") (class "Default")
      (node (ref "LED4") (pin "A") (pinfunction "A_A") (pintype "passive"))
      (node (ref "R29") (pin "1") (pinfunction "1_1") (pintype "passive"))
    )
    (net (code "50") (name "Net-(OK1A-A1)") (class "Default")
      (node (ref "OK1") (pin "1") (pinfunction "A1_1") (pintype "passive"))
      (node (ref "R10") (pin "1") (pinfunction "1_1") (pintype "passive"))
    )
    (net (code "51") (name "Net-(OK1A-VCC)") (class "Default")
      (node (ref "C9") (pin "2") (pinfunction "2_2") (pintype "passive"))
      (node (ref "OK1") (pin "8") (pinfunction "VCC_8") (pintype "passive"))
      (node (ref "R8") (pin "1") (pinfunction "1_1") (pintype "passive"))
    )
    (net (code "52") (name "Net-(OK1B-A2)") (class "Default")
      (node (ref "OK1") (pin "4") (pinfunction "A2_4") (pintype "passive"))
      (node (ref "R12") (pin "1") (pinfunction "1_1") (pintype "passive"))
    )
    (net (code "53") (name "Net-(OK2A-A1)") (class "Default")
      (node (ref "OK2") (pin "1") (pinfunction "A1_1") (pintype "passive"))
      (node (ref "R15") (pin "1") (pinfunction "1_1") (pintype "passive"))
    )
    (net (code "54") (name "Net-(OK2A-VCC)") (class "Default")
      (node (ref "C10") (pin "2") (pinfunction "2_2") (pintype "passive"))
      (node (ref "OK2") (pin "8") (pinfunction "VCC_8") (pintype "passive"))
      (node (ref "R13") (pin "1") (pinfunction "1_1") (pintype "passive"))
    )
    (net (code "55") (name "Net-(OK2B-A2)") (class "Default")
      (node (ref "OK2") (pin "4") (pinfunction "A2_4") (pintype "passive"))
      (node (ref "R17") (pin "1") (pinfunction "1_1") (pintype "passive"))
    )
    (net (code "56") (name "Net-(OK3A-A1)") (class "Default")
      (node (ref "OK3") (pin "1") (pinfunction "A1_1") (pintype "passive"))
      (node (ref "R20") (pin "1") (pinfunction "1_1") (pintype "passive"))
    )
    (net (code "57") (name "Net-(OK3A-VCC)") (class "Default")
      (node (ref "C11") (pin "2") (pinfunction "2_2") (pintype "passive"))
      (node (ref "OK3") (pin "8") (pinfunction "VCC_8") (pintype "passive"))
      (node (ref "R18") (pin "1") (pinfunction "1_1") (pintype "passive"))
    )
    (net (code "58") (name "Net-(OK3B-A2)") (class "Default")
      (node (ref "OK3") (pin "4") (pinfunction "A2_4") (pintype "passive"))
      (node (ref "R22") (pin "1") (pinfunction "1_1") (pintype "passive"))
    )
    (net (code "59") (name "Net-(OK4A-A1)") (class "Default")
      (node (ref "OK4") (pin "1") (pinfunction "A1_1") (pintype "passive"))
      (node (ref "R25") (pin "1") (pinfunction "1_1") (pintype "passive"))
    )
    (net (code "60") (name "Net-(OK4A-VCC)") (class "Default")
      (node (ref "C14") (pin "2") (pinfunction "2_2") (pintype "passive"))
      (node (ref "OK4") (pin "8") (pinfunction "VCC_8") (pintype "passive"))
      (node (ref "R23") (pin "1") (pinfunction "1_1") (pintype "passive"))
    )
    (net (code "61") (name "Net-(OK4B-A2)") (class "Default")
      (node (ref "OK4") (pin "4") (pinfunction "A2_4") (pintype "passive"))
      (node (ref "R37") (pin "1") (pinfunction "1_1") (pintype "passive"))
    )
    (net (code "62") (name "Net-(OK5A-A1)") (class "Default")
      (node (ref "OK5") (pin "1") (pinfunction "A1_1") (pintype "passive"))
      (node (ref "R39") (pin "1") (pinfunction "1_1") (pintype "passive"))
    )
    (net (code "63") (name "Net-(OK5A-VCC)") (class "Default")
      (node (ref "C15") (pin "2") (pinfunction "2_2") (pintype "passive"))
      (node (ref "OK5") (pin "8") (pinfunction "VCC_8") (pintype "passive"))
      (node (ref "R26") (pin "1") (pinfunction "1_1") (pintype "passive"))
    )
    (net (code "64") (name "Net-(OK5B-A2)") (class "Default")
      (node (ref "OK5") (pin "4") (pinfunction "A2_4") (pintype "passive"))
      (node (ref "R41") (pin "1") (pinfunction "1_1") (pintype "passive"))
    )
    (net (code "65") (name "Net-(Q5-G)") (class "Default")
      (node (ref "Q5") (pin "1") (pinfunction "G_1") (pintype "bidirectional"))
      (node (ref "R30") (pin "1") (pinfunction "1_1") (pintype "passive"))
    )
    (net (code "66") (name "Net-(Q6-G)") (class "Default")
      (node (ref "Q6") (pin "1") (pinfunction "G_1") (pintype "bidirectional"))
      (node (ref "R31") (pin "1") (pinfunction "1_1") (pintype "passive"))
    )
    (net (code "67") (name "Net-(Q7-G)") (class "Default")
      (node (ref "Q7") (pin "1") (pinfunction "G_1") (pintype "bidirectional"))
      (node (ref "R32") (pin "2") (pinfunction "2_2") (pintype "passive"))
    )
    (net (code "68") (name "Net-(Q8-G)") (class "Default")
      (node (ref "Q8") (pin "1") (pinfunction "G_1") (pintype "bidirectional"))
      (node (ref "R33") (pin "2") (pinfunction "2_2") (pintype "passive"))
    )
    (net (code "69") (name "Net-(Q9-G)") (class "Default")
      (node (ref "Q9") (pin "1") (pinfunction "G_1") (pintype "bidirectional"))
      (node (ref "R34") (pin "2") (pinfunction "2_2") (pintype "passive"))
    )
    (net (code "70") (name "Net-(Q10-G)") (class "Default")
      (node (ref "Q10") (pin "1") (pinfunction "G_1") (pintype "bidirectional"))
      (node (ref "R35") (pin "2") (pinfunction "2_2") (pintype "passive"))
    )
    (net (code "71") (name "Net-(U$1-RA6{slash}CLKOUT)") (class "Default")
      (node (ref "U$1") (pin "14") (pinfunction "RA6/CLKOUT_14") (pintype "bidirectional"))
      (node (ref "X2") (pin "1") (pinfunction "1_1") (pintype "passive"))
    )
    (net (code "72") (name "Net-(U$1-RB0)") (class "Default")
      (node (ref "R30") (pin "2") (pinfunction "2_2") (pintype "passive"))
      (node (ref "U$1") (pin "33") (pinfunction "RB0_33") (pintype "bidirectional"))
    )
    (net (code "73") (name "Net-(U$1-RB1)") (class "Default")
      (node (ref "R31") (pin "2") (pinfunction "2_2") (pintype "passive"))
      (node (ref "U$1") (pin "34") (pinfunction "RB1_34") (pintype "bidirectional"))
    )
    (net (code "74") (name "Net-(U$1-RB6{slash}PGC)") (class "Default")
      (node (ref "U$1") (pin "39") (pinfunction "RB6/PGC_39") (pintype "bidirectional"))
      (node (ref "X1") (pin "5") (pinfunction "S_5") (pintype "passive"))
    )
    (net (code "75") (name "Net-(U$1-RB7{slash}PGD)") (class "Default")
      (node (ref "U$1") (pin "40") (pinfunction "RB7/PGD_40") (pintype "bidirectional"))
      (node (ref "X1") (pin "4") (pinfunction "S_4") (pintype "passive"))
    )
    (net (code "76") (name "Net-(U$1-RC2)") (class "Default")
      (node (ref "R28") (pin "2") (pinfunction "2_2") (pintype "passive"))
      (node (ref "U$1") (pin "17") (pinfunction "RC2_17") (pintype "bidirectional"))
    )
    (net (code "77") (name "Net-(U$1-RC3)") (class "Default")
      (node (ref "R29") (pin "2") (pinfunction "2_2") (pintype "passive"))
      (node (ref "U$1") (pin "18") (pinfunction "RC3_18") (pintype "bidirectional"))
    )
    (net (code "78") (name "Net-(U$1-RC5)") (class "Default")
      (node (ref "U$1") (pin "24") (pinfunction "RC5_24") (pintype "bidirectional"))
      (node (ref "X3") (pin "1") (pinfunction "P_1") (pintype "passive"))
    )
    (net (code "79") (name "Net-(U$1-RC6)") (class "Default")
      (node (ref "U$1") (pin "25") (pinfunction "RC6_25") (pintype "bidirectional"))
      (node (ref "X4") (pin "1") (pinfunction "P_1") (pintype "passive"))
    )
    (net (code "80") (name "Net-(U$1-RE3{slash}~{MCLR})") (class "Default")
      (node (ref "R3") (pin "2") (pinfunction "2_2") (pintype "passive"))
      (node (ref "RST") (pin "1") (pinfunction "1_1") (pintype "passive"))
      (node (ref "U$1") (pin "1") (pinfunction "RE3/~{MCLR}_1") (pintype "bidirectional"))
      (node (ref "X1") (pin "1") (pinfunction "S_1") (pintype "passive"))
    )
    (net (code "81") (name "VCC") (class "Default")
      (node (ref "L1") (pin "P$1") (pinfunction "1_P$1") (pintype "passive"))
      (node (ref "R1") (pin "1") (pinfunction "1_1") (pintype "passive"))
      (node (ref "VCC") (pin "1") (pinfunction "P_1") (pintype "passive"))
    )
    (net (code "82") (name "unconnected-(U$1-RC0-Pad15)") (class "Default")
      (node (ref "U$1") (pin "15") (pinfunction "RC0_15") (pintype "bidirectional"))
    )
    (net (code "83") (name "unconnected-(U$1-RC1-Pad16)") (class "Default")
      (node (ref "U$1") (pin "16") (pinfunction "RC1_16") (pintype "bidirectional"))
    )
    (net (code "84") (name "unconnected-(U$1-RC4-Pad23)") (class "Default")
      (node (ref "U$1") (pin "23") (pinfunction "RC4_23") (pintype "bidirectional"))
    )
    (net (code "85") (name "unconnected-(U$1-RC7-Pad26)") (class "Default")
      (node (ref "U$1") (pin "26") (pinfunction "RC7_26") (pintype "bidirectional"))
    )
    (net (code "86") (name "unconnected-(U$1-RD2-Pad21)") (class "Default")
      (node (ref "U$1") (pin "21") (pinfunction "RD2_21") (pintype "bidirectional"))
    )
    (net (code "87") (name "unconnected-(U$1-RD3-Pad22)") (class "Default")
      (node (ref "U$1") (pin "22") (pinfunction "RD3_22") (pintype "bidirectional"))
    )
    (net (code "88") (name "unconnected-(U$1-RE1-Pad9)") (class "Default")
      (node (ref "U$1") (pin "9") (pinfunction "RE1_9") (pintype "bidirectional"))
    )
    (net (code "89") (name "unconnected-(U$1-RE2-Pad10)") (class "Default")
      (node (ref "U$1") (pin "10") (pinfunction "RE2_10") (pintype "bidirectional"))
    )
  )
)
